# Power.net
KiCad netlist of a schematic drawn in Altium Designer
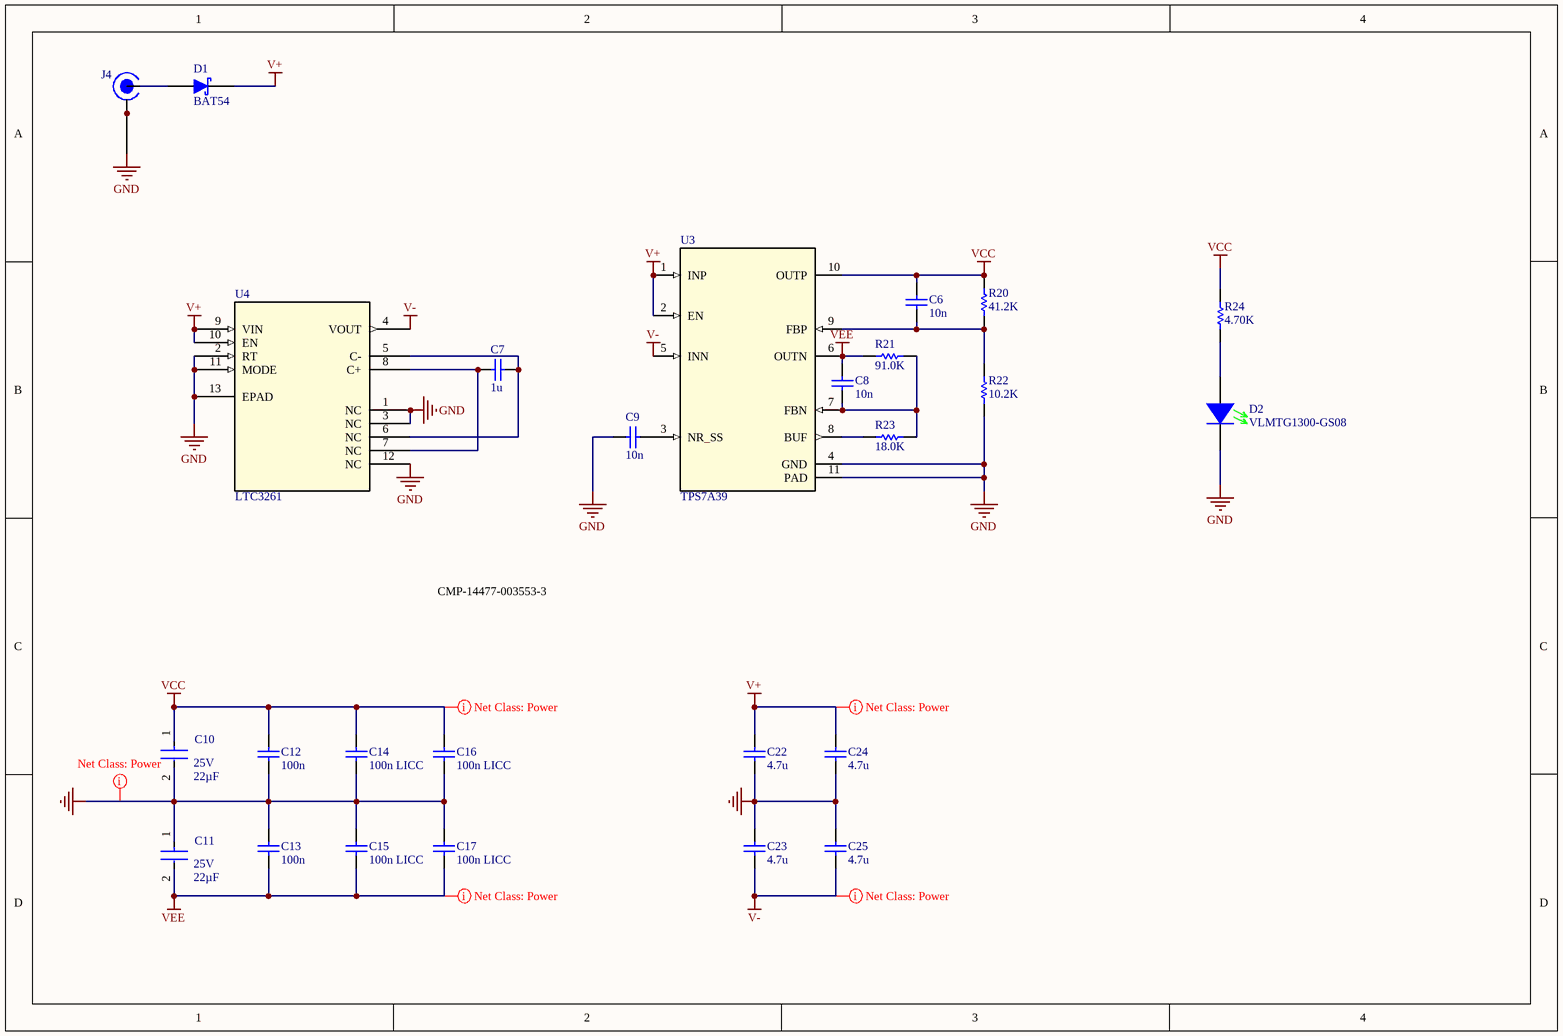
[diagram p0: Power.SchDoc]

(export (version "E")
  (design (tool "Eeschema 10.0.6"))
  (components
    (comp (ref "C6")
      (value "10n")
      (footprint "CAPC0402(1005)50_M")
      (description "CAP CER 10NF±5% 25V C0G 0402")
      (fields
        (field (name "MANUFACTURER") "Murata")
        (field (name "MANUFACTURER PART NUMBER") "GRM1555C1E103JE01D")
      )
      (libsource (lib "Murata GRM 0402") (part "Capacitor_Generic"))
    )
    (comp (ref "C7")
      (value "1u")
      (footprint "CAPC0805(2012)145_M")
      (description "Cap Ceramic 1uF 50V X7R 10% SMD 0805 125C Blister T/R")
      (fields
        (field (name "MANUFACTURER") "Yageo")
        (field (name "MANUFACTURER PART NUMBER") "CC0805KKX7R9BB105")
      )
      (libsource (lib "0805 Caps") (part "CC0805KKX7R9BB105"))
    )
    (comp (ref "C8")
      (value "10n")
      (footprint "CAPC0402(1005)50_M")
      (description "CAP CER 10NF±5% 25V C0G 0402")
      (fields
        (field (name "MANUFACTURER") "Murata")
        (field (name "MANUFACTURER PART NUMBER") "GRM1555C1E103JE01D")
      )
      (libsource (lib "Murata GRM 0402") (part "Capacitor_Generic"))
    )
    (comp (ref "C9")
      (value "10n")
      (footprint "CAPC0402(1005)50_M")
      (description "CAP CER 10NF±5% 25V C0G 0402")
      (fields
        (field (name "MANUFACTURER") "Murata")
        (field (name "MANUFACTURER PART NUMBER") "GRM1555C1E103JE01D")
      )
      (libsource (lib "Murata GRM 0402") (part "Capacitor_Generic"))
    )
    (comp (ref "C10")
      (value "CL31A226KAHNNNE")
      (footprint "CL31H-0_2_MFG")
      (fields (field (name "TOLERANCE") "10%"))
      (libsource (lib "Altium Content Vault") (part "fb88589c83559698c54462c48d907c3"))
    )
    (comp (ref "C11")
      (value "CL31A226KAHNNNE")
      (footprint "CL31H-0_2_MFG")
      (fields (field (name "TOLERANCE") "10%"))
      (libsource (lib "Altium Content Vault") (part "fb88589c83559698c54462c48d907c3"))
    )
    (comp (ref "C12")
      (value "100n")
      (footprint "CAPC0603(1608)100_M")
      (description "CAPACITOR CERAMIC, 0.1UF, 50V, X7R, 10%, 0603")
      (fields
        (field (name "MANUFACTURER") "Yageo")
        (field (name "MANUFACTURER PART NUMBER") "CC0603KRX7R9BB104")
      )
      (libsource (lib "0603 Caps") (part "CC0603KRX7R9BB104"))
    )
    (comp (ref "C13")
      (value "100n")
      (footprint "CAPC0603(1608)100_M")
      (description "CAPACITOR CERAMIC, 0.1UF, 50V, X7R, 10%, 0603")
      (fields
        (field (name "MANUFACTURER") "Yageo")
        (field (name "MANUFACTURER PART NUMBER") "CC0603KRX7R9BB104")
      )
      (libsource (lib "0603 Caps") (part "CC0603KRX7R9BB104"))
    )
    (comp (ref "C14")
      (value "100n LICC")
      (footprint "CAPC0306_M")
      (description "CAP CER 0.1UF 25V X7R 0306")
      (fields
        (field (name "MANUFACTURER") "Taiyo Yuden")
        (field (name "MANUFACTURER PART NUMBER") "TWK107B7104MVHT")
      )
      (libsource (lib "Misc Caps") (part "TWK107B7104MVHT"))
    )
    (comp (ref "C15")
      (value "100n LICC")
      (footprint "CAPC0306_M")
      (description "CAP CER 0.1UF 25V X7R 0306")
      (fields
        (field (name "MANUFACTURER") "Taiyo Yuden")
        (field (name "MANUFACTURER PART NUMBER") "TWK107B7104MVHT")
      )
      (libsource (lib "Misc Caps") (part "TWK107B7104MVHT"))
    )
    (comp (ref "C16")
      (value "100n LICC")
      (footprint "CAPC0306_M")
      (description "CAP CER 0.1UF 25V X7R 0306")
      (fields
        (field (name "MANUFACTURER") "Taiyo Yuden")
        (field (name "MANUFACTURER PART NUMBER") "TWK107B7104MVHT")
      )
      (libsource (lib "Misc Caps") (part "TWK107B7104MVHT"))
    )
    (comp (ref "C17")
      (value "100n LICC")
      (footprint "CAPC0306_M")
      (description "CAP CER 0.1UF 25V X7R 0306")
      (fields
        (field (name "MANUFACTURER") "Taiyo Yuden")
        (field (name "MANUFACTURER PART NUMBER") "TWK107B7104MVHT")
      )
      (libsource (lib "Misc Caps") (part "TWK107B7104MVHT"))
    )
    (comp (ref "C22")
      (value "4.7u")
      (footprint "CAPC0805(2012)100_M")
      (description "CAP CER 4.7UF 50V X7R 0805")
      (fields
        (field (name "MANUFACTURER") "Murata")
        (field (name "MANUFACTURER PART NUMBER") "GRM21BZ71H475KE15K")
      )
      (libsource (lib "0805 Caps") (part "GRM21BZ71H475KE15K"))
    )
    (comp (ref "C23")
      (value "4.7u")
      (footprint "CAPC0805(2012)100_M")
      (description "CAP CER 4.7UF 50V X7R 0805")
      (fields
        (field (name "MANUFACTURER") "Murata")
        (field (name "MANUFACTURER PART NUMBER") "GRM21BZ71H475KE15K")
      )
      (libsource (lib "0805 Caps") (part "GRM21BZ71H475KE15K"))
    )
    (comp (ref "C24")
      (value "4.7u")
      (footprint "CAPC0805(2012)100_M")
      (description "CAP CER 4.7UF 50V X7R 0805")
      (fields
        (field (name "MANUFACTURER") "Murata")
        (field (name "MANUFACTURER PART NUMBER") "GRM21BZ71H475KE15K")
      )
      (libsource (lib "0805 Caps") (part "GRM21BZ71H475KE15K"))
    )
    (comp (ref "C25")
      (value "4.7u")
      (footprint "CAPC0805(2012)100_M")
      (description "CAP CER 4.7UF 50V X7R 0805")
      (fields
        (field (name "MANUFACTURER") "Murata")
        (field (name "MANUFACTURER PART NUMBER") "GRM21BZ71H475KE15K")
      )
      (libsource (lib "0805 Caps") (part "GRM21BZ71H475KE15K"))
    )
    (comp (ref "D1")
      (value "BAT54")
      (footprint "INF-PG-SC59_M")
      (description "DIODE SCHOTTKY 30V 200MA TO236AB")
      (fields
        (field (name "MANUFACTURER") "Nexperia USA")
        (field (name "MANUFACTURER PART NUMBER") "BAT54,215")
      )
      (libsource (lib "Discretes") (part "BAT54"))
    )
    (comp (ref "D2")
      (value "VLMTG1300-GS08")
      (footprint "LED0603(1608)_M")
      (description "LED GREEN 0603 SMD")
      (fields (field (name "MANUFACTURER") "Vishay Semiconductors"))
      (libsource (lib "Discretes") (part "VLMTG1300-GS08"))
    )
    (comp (ref "J4")
      (value "2.1/5.5mm")
      (footprint "CUI PJ-002A")
      (description "CONN PWR JACK 2X5.5MM SOLDER")
      (fields (field (name "MANUFACTURER") "CUI") (field (name "MANUFACTURER PART NUMBER") "PJ-002A"))
      (libsource (lib "Connectors") (part "PJ-002A"))
    )
    (comp (ref "R20")
      (value "41.2K")
      (footprint "RESC0402(1005)_M")
      (description "RES 41.2K OHM 1% 1/16W 0402")
      (fields (field (name "PART NUMBER") "RESC0402-41K2-1pct"))
      (libsource (lib "R0402 - 1pct") (part "Resistor_Generic"))
    )
    (comp (ref "R21")
      (value "91.0K")
      (footprint "RESC0402(1005)_M")
      (description "RES 91.0K OHM 1% 1/16W 0402")
      (fields (field (name "PART NUMBER") "RESC0402-91K0-1pct"))
      (libsource (lib "R0402 - 1pct") (part "Resistor_Generic"))
    )
    (comp (ref "R22")
      (value "10.2K")
      (footprint "RESC0402(1005)_M")
      (description "RES 10.2K OHM 1% 1/16W 0402")
      (fields (field (name "PART NUMBER") "RESC0402-10K2-1pct"))
      (libsource (lib "R0402 - 1pct") (part "Resistor_Generic"))
    )
    (comp (ref "R23")
      (value "18.0K")
      (footprint "RESC0402(1005)_M")
      (description "RES 18.0K OHM 1% 1/16W 0402")
      (fields (field (name "PART NUMBER") "RESC0402-18K0-1pct"))
      (libsource (lib "R0402 - 1pct") (part "Resistor_Generic"))
    )
    (comp (ref "R24")
      (value "4.70K")
      (footprint "RESC0603(1608)_M")
      (description "RES 4.70K OHM 1% 1/10W 0603")
      (fields (field (name "PART NUMBER") "RESC0603-4K70-1pct"))
      (libsource (lib "R0603 - 1pct") (part "Resistor_Generic"))
    )
    (comp (ref "U3")
      (value "TPS7A39")
      (footprint "DSC0010J_NV")
      (description "IC REG LINEAR POS/NEG ADJ 10WSON")
      (fields
        (field (name "MANUFACTURER_PART_NUMBER") "TPS7A3901DSCR")
        (field (name "MANUFACTURER") "Texas Instruments")
        (field (name "COPYRIGHT") "Copyright (C) 2022 Ultra Librarian. All rights reserved.")
      )
      (libsource (lib "IC") (part "TPS7A3901DSCR"))
    )
    (comp (ref "U4")
      (value "LTC3261")
      (footprint "MSOP-12_MSE")
      (description "IC REG CHARG PUMP INV 12MSOP")
      (fields
        (field (name "MANUFACTURER_PART_NUMBER") "ltc3261emse#pbf")
        (field (name "MANUFACTURER") "Analog Devices / Linear Technology")
        (field (name "COPYRIGHT") "Copyright (C) 2022 Ultra Librarian. All rights reserved.")
      )
      (libsource (lib "IC") (part "LTC3261EMSE"))
    )
  )
  (nets
    (net (code "1") (name "GND") (class "Default")
      (node (ref "C10") (pin "2") (pinfunction "2_2") (pintype "passive"))
      (node (ref "C11") (pin "1") (pinfunction "1_1") (pintype "passive"))
      (node (ref "C12") (pin "2") (pinfunction "2_2") (pintype "passive"))
      (node (ref "C13") (pin "1") (pinfunction "1_1") (pintype "passive"))
      (node (ref "C14") (pin "2") (pinfunction "2_2") (pintype "passive"))
      (node (ref "C15") (pin "1") (pinfunction "1_1") (pintype "passive"))
      (node (ref "C16") (pin "2") (pinfunction "2_2") (pintype "passive"))
      (node (ref "C17") (pin "1") (pinfunction "1_1") (pintype "passive"))
      (node (ref "C22") (pin "2") (pinfunction "2_2") (pintype "passive"))
      (node (ref "C23") (pin "1") (pinfunction "1_1") (pintype "passive"))
      (node (ref "C24") (pin "2") (pinfunction "2_2") (pintype "passive"))
      (node (ref "C25") (pin "2") (pinfunction "2_2") (pintype "passive"))
      (node (ref "C9") (pin "2") (pinfunction "2_2") (pintype "passive"))
      (node (ref "D2") (pin "2") (pinfunction "K_2") (pintype "passive"))
      (node (ref "J4") (pin "2") (pinfunction "2_2") (pintype "passive"))
      (node (ref "J4") (pin "3") (pinfunction "3_3") (pintype "passive"))
      (node (ref "R22") (pin "2") (pinfunction "2_2") (pintype "passive"))
      (node (ref "U3") (pin "11") (pinfunction "PAD_11") (pintype "power_in"))
      (node (ref "U3") (pin "4") (pinfunction "GND_4") (pintype "power_in"))
      (node (ref "U4") (pin "1") (pinfunction "NC_1") (pintype "passive"))
      (node (ref "U4") (pin "11") (pinfunction "MODE_11") (pintype "input"))
      (node (ref "U4") (pin "12") (pinfunction "NC_12") (pintype "passive"))
      (node (ref "U4") (pin "13") (pinfunction "EPAD_13") (pintype "passive"))
      (node (ref "U4") (pin "2") (pinfunction "RT_2") (pintype "input"))
      (node (ref "U4") (pin "3") (pinfunction "NC_3") (pintype "passive"))
    )
    (net (code "2") (name "Net-(D1-A)") (class "Default")
      (node (ref "D1") (pin "1") (pinfunction "A_1") (pintype "passive"))
      (node (ref "J4") (pin "1") (pinfunction "1_1") (pintype "passive"))
    )
    (net (code "3") (name "Net-(D2-A)") (class "Default")
      (node (ref "D2") (pin "1") (pinfunction "A_1") (pintype "passive"))
      (node (ref "R24") (pin "2") (pinfunction "2_2") (pintype "passive"))
    )
    (net (code "4") (name "Net-(U3-BUF)") (class "Default")
      (node (ref "R23") (pin "2") (pinfunction "2_2") (pintype "passive"))
      (node (ref "U3") (pin "8") (pinfunction "BUF_8") (pintype "output"))
    )
    (net (code "5") (name "Net-(U3-FBN)") (class "Default")
      (node (ref "C8") (pin "1") (pinfunction "1_1") (pintype "passive"))
      (node (ref "R21") (pin "1") (pinfunction "1_1") (pintype "passive"))
      (node (ref "R23") (pin "1") (pinfunction "1_1") (pintype "passive"))
      (node (ref "U3") (pin "7") (pinfunction "FBN_7") (pintype "input"))
    )
    (net (code "6") (name "Net-(U3-FBP)") (class "Default")
      (node (ref "C6") (pin "1") (pinfunction "1_1") (pintype "passive"))
      (node (ref "R20") (pin "2") (pinfunction "2_2") (pintype "passive"))
      (node (ref "R22") (pin "1") (pinfunction "1_1") (pintype "passive"))
      (node (ref "U3") (pin "9") (pinfunction "FBP_9") (pintype "input"))
    )
    (net (code "7") (name "Net-(U3-NR_SS)") (class "Default")
      (node (ref "C9") (pin "1") (pinfunction "1_1") (pintype "passive"))
      (node (ref "U3") (pin "3") (pinfunction "NR_SS_3") (pintype "input"))
    )
    (net (code "8") (name "Net-(U4-C+)") (class "Default")
      (node (ref "C7") (pin "1") (pinfunction "1_1") (pintype "passive"))
      (node (ref "U4") (pin "7") (pinfunction "NC_7") (pintype "passive"))
      (node (ref "U4") (pin "8") (pinfunction "C+_8") (pintype "passive"))
    )
    (net (code "9") (name "Net-(U4-C-)") (class "Default")
      (node (ref "C7") (pin "2") (pinfunction "2_2") (pintype "passive"))
      (node (ref "U4") (pin "5") (pinfunction "C-_5") (pintype "passive"))
      (node (ref "U4") (pin "6") (pinfunction "NC_6") (pintype "passive"))
    )
    (net (code "10") (name "V+") (class "Default")
      (node (ref "C22") (pin "1") (pinfunction "1_1") (pintype "passive"))
      (node (ref "C24") (pin "1") (pinfunction "1_1") (pintype "passive"))
      (node (ref "D1") (pin "3") (pinfunction "K_3") (pintype "passive"))
      (node (ref "U3") (pin "1") (pinfunction "INP_1") (pintype "input"))
      (node (ref "U3") (pin "2") (pinfunction "EN_2") (pintype "input"))
      (node (ref "U4") (pin "10") (pinfunction "EN_10") (pintype "input"))
      (node (ref "U4") (pin "9") (pinfunction "VIN_9") (pintype "input"))
    )
    (net (code "11") (name "V-") (class "Default")
      (node (ref "C23") (pin "2") (pinfunction "2_2") (pintype "passive"))
      (node (ref "C25") (pin "1") (pinfunction "1_1") (pintype "passive"))
      (node (ref "U3") (pin "5") (pinfunction "INN_5") (pintype "input"))
      (node (ref "U4") (pin "4") (pinfunction "VOUT_4") (pintype "output"))
    )
    (net (code "12") (name "VCC") (class "Default")
      (node (ref "C10") (pin "1") (pinfunction "1_1") (pintype "passive"))
      (node (ref "C12") (pin "1") (pinfunction "1_1") (pintype "passive"))
      (node (ref "C14") (pin "1") (pinfunction "1_1") (pintype "passive"))
      (node (ref "C16") (pin "1") (pinfunction "1_1") (pintype "passive"))
      (node (ref "C6") (pin "2") (pinfunction "2_2") (pintype "passive"))
      (node (ref "R20") (pin "1") (pinfunction "1_1") (pintype "passive"))
      (node (ref "R24") (pin "1") (pinfunction "1_1") (pintype "passive"))
      (node (ref "U3") (pin "10") (pinfunction "OUTP_10") (pintype "power_in"))
    )
    (net (code "13") (name "VEE") (class "Default")
      (node (ref "C11") (pin "2") (pinfunction "2_2") (pintype "passive"))
      (node (ref "C13") (pin "2") (pinfunction "2_2") (pintype "passive"))
      (node (ref "C15") (pin "2") (pinfunction "2_2") (pintype "passive"))
      (node (ref "C17") (pin "2") (pinfunction "2_2") (pintype "passive"))
      (node (ref "C8") (pin "2") (pinfunction "2_2") (pintype "passive"))
      (node (ref "R21") (pin "2") (pinfunction "2_2") (pintype "passive"))
      (node (ref "U3") (pin "6") (pinfunction "OUTN_6") (pintype "power_in"))
    )
  )
)
